# MCP9808.net
KiCad netlist of a schematic drawn in EAGLE
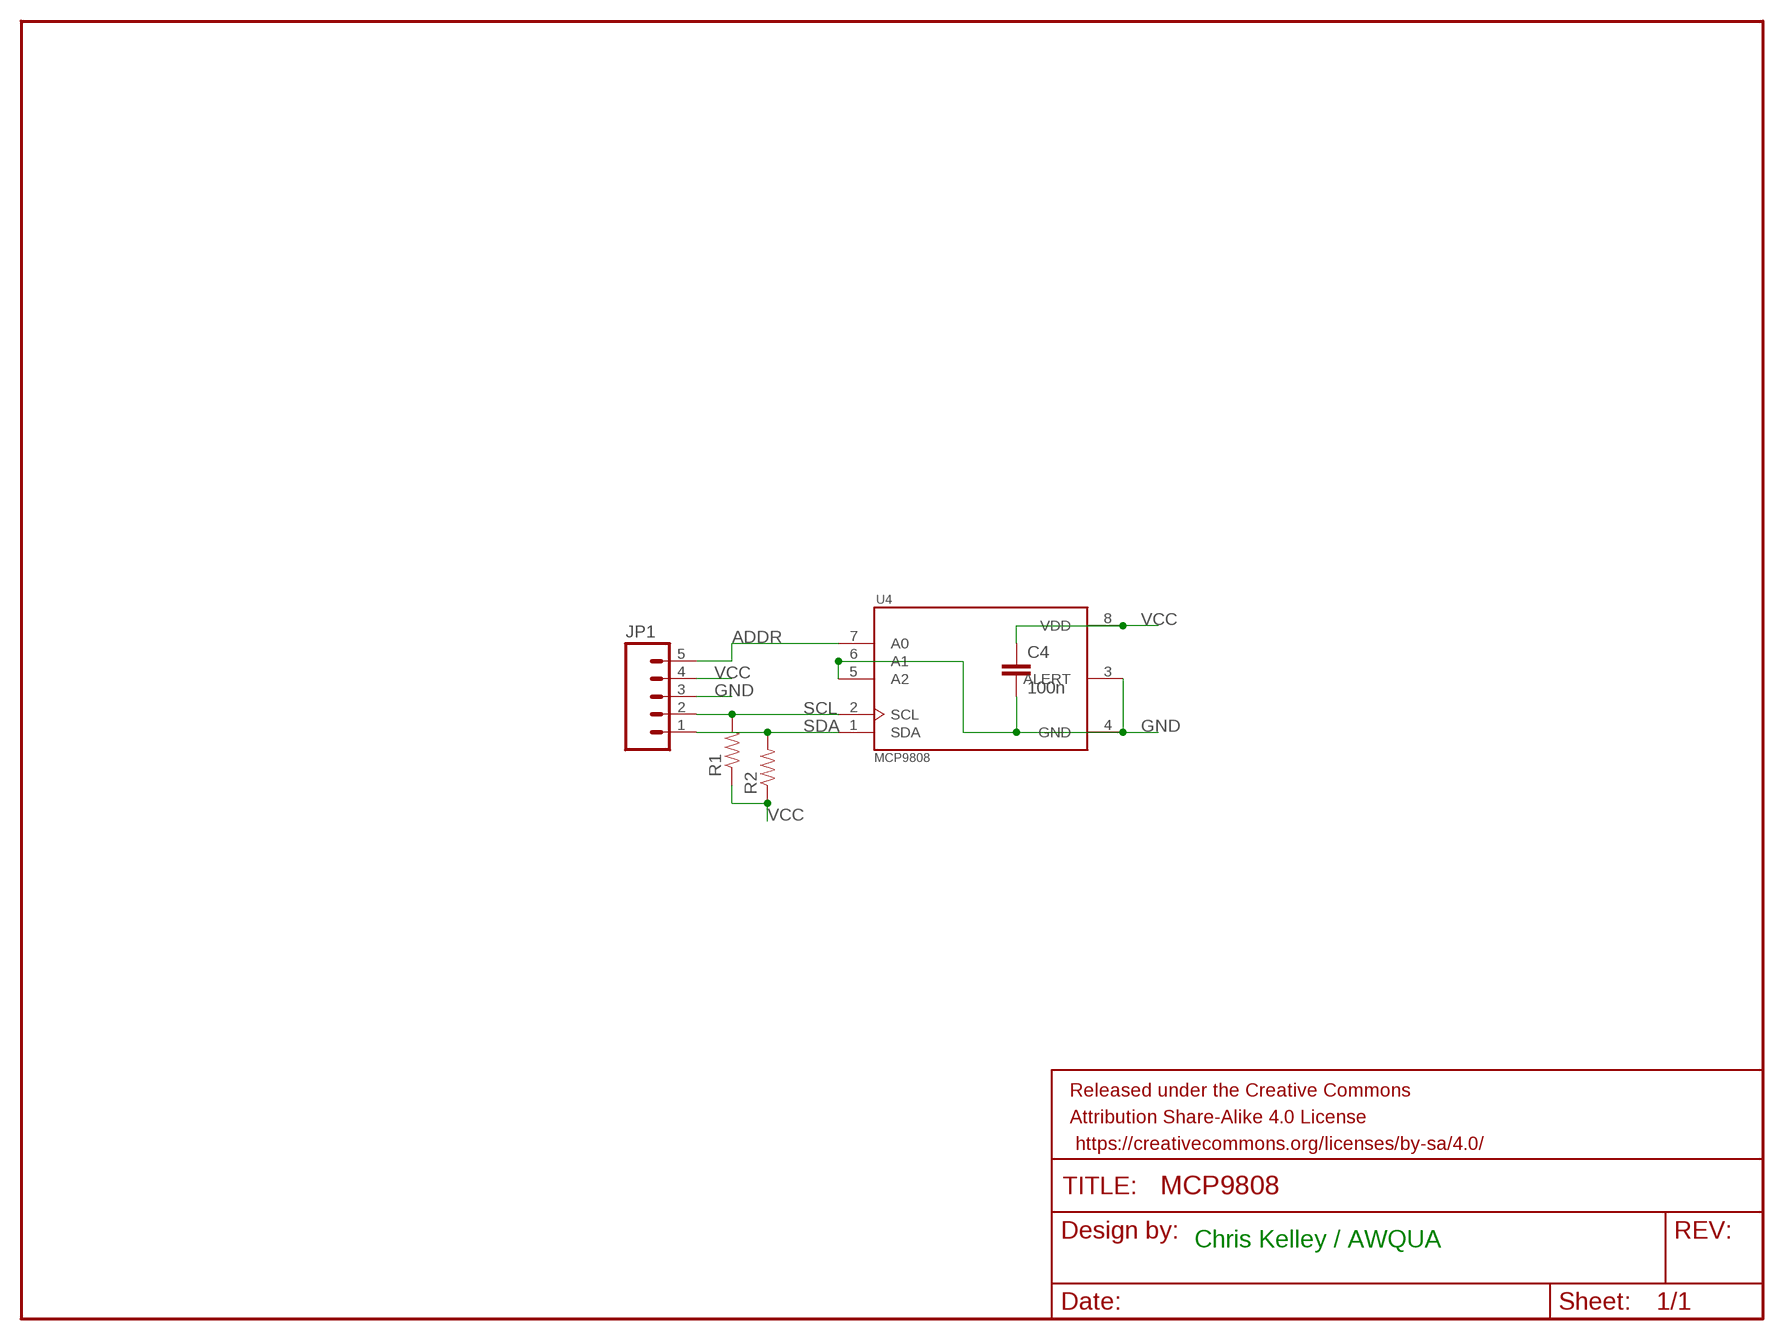
[diagram p0: schematic, sheet 1]

(export (version "E")
  (design (tool "Eeschema 10.0.6"))
  (components
    (comp (ref "C4")
      (value "100n")
      (footprint "eagle-import:0603-CAP")
      (libsource (lib "eagle-import") (part "CAP0603-CAP"))
    )
    (comp (ref "FRAME1")
      (value "FRAME-LETTER")
      (footprint "eagle-import:CREATIVE_COMMONS")
      (libsource (lib "eagle-import") (part "FRAME-LETTER"))
    )
    (comp (ref "JP1")
      (value "M05PTH")
      (footprint "eagle-import:1X05")
      (libsource (lib "eagle-import") (part "M05PTH"))
    )
    (comp (ref "R1")
      (value "RESISTOR0603-RES")
      (footprint "eagle-import:0603-RES")
      (libsource (lib "eagle-import") (part "RESISTOR0603-RES"))
    )
    (comp (ref "R2")
      (value "RESISTOR0603-RES")
      (footprint "eagle-import:0603-RES")
      (libsource (lib "eagle-import") (part "RESISTOR0603-RES"))
    )
    (comp (ref "U4")
      (value "MCP9808")
      (footprint "eagle-import:SOP65P490X110-8N")
      (fields (field (name "MF") "Microchip") (field (name "MP") "MCP9808-E/MS"))
      (libsource (lib "eagle-import") (part "MCP9808-E/MS"))
    )
  )
  (nets
    (net (code "1") (name "/ADDR") (class "Default")
      (node (ref "JP1") (pin "5") (pinfunction "5_5") (pintype "passive"))
      (node (ref "U4") (pin "7") (pinfunction "A0_7") (pintype "input"))
    )
    (net (code "2") (name "/GND") (class "Default")
      (node (ref "C4") (pin "2") (pinfunction "2_2") (pintype "passive"))
      (node (ref "JP1") (pin "3") (pinfunction "3_3") (pintype "passive"))
      (node (ref "U4") (pin "3") (pinfunction "ALERT_3") (pintype "output"))
      (node (ref "U4") (pin "4") (pinfunction "GND_4") (pintype "power_in"))
      (node (ref "U4") (pin "5") (pinfunction "A2_5") (pintype "input"))
      (node (ref "U4") (pin "6") (pinfunction "A1_6") (pintype "input"))
    )
    (net (code "3") (name "/SCL") (class "Default")
      (node (ref "JP1") (pin "2") (pinfunction "2_2") (pintype "passive"))
      (node (ref "R1") (pin "2") (pinfunction "2_2") (pintype "passive"))
      (node (ref "U4") (pin "2") (pinfunction "SCL_2") (pintype "input"))
    )
    (net (code "4") (name "/SDA") (class "Default")
      (node (ref "JP1") (pin "1") (pinfunction "1_1") (pintype "passive"))
      (node (ref "R2") (pin "2") (pinfunction "2_2") (pintype "passive"))
      (node (ref "U4") (pin "1") (pinfunction "SDA_1") (pintype "bidirectional"))
    )
    (net (code "5") (name "/VCC") (class "Default")
      (node (ref "C4") (pin "1") (pinfunction "1_1") (pintype "passive"))
      (node (ref "JP1") (pin "4") (pinfunction "4_4") (pintype "passive"))
      (node (ref "R1") (pin "1") (pinfunction "1_1") (pintype "passive"))
      (node (ref "R2") (pin "1") (pinfunction "1_1") (pintype "passive"))
      (node (ref "U4") (pin "8") (pinfunction "VDD_8") (pintype "power_in"))
    )
  )
)
